# Serial-7-Segment-Shield.net
KiCad netlist of a schematic drawn in EAGLE
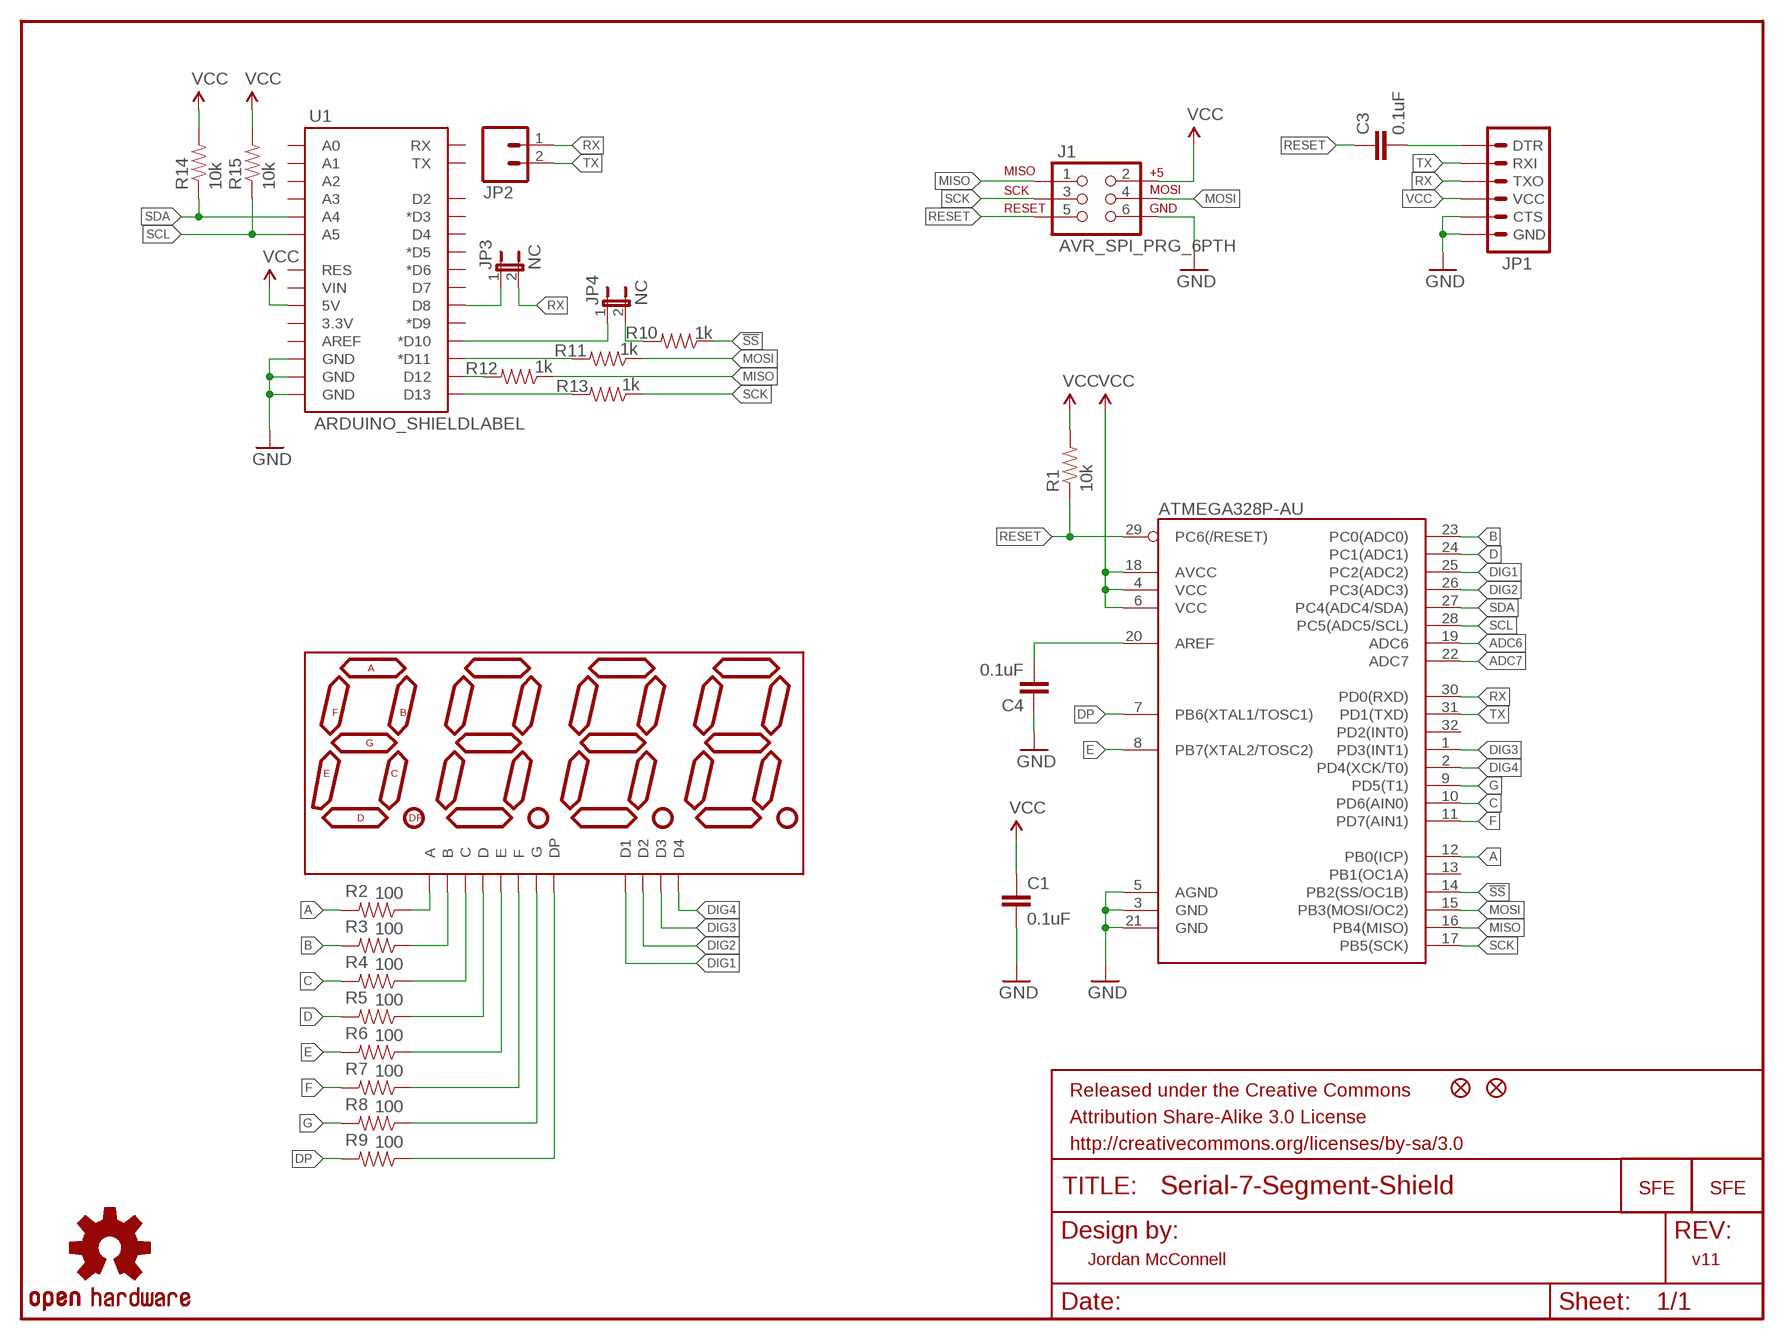
[diagram p0: schematic, sheet 1]

(export (version "E")
  (design (tool "Eeschema 10.0.6"))
  (components
    (comp (ref "ATMEGA328P-AU")
      (value "ATMEGA328P-AU")
      (footprint "eagle-import:TQFP32-08")
      (libsource (lib "eagle-import") (part "ATMEGA168"))
    )
    (comp (ref "C1")
      (value "0.1uF")
      (footprint "eagle-import:0603-CAP")
      (libsource (lib "eagle-import") (part "CAP0603-CAP"))
    )
    (comp (ref "C3")
      (value "0.1uF")
      (footprint "eagle-import:0603-CAP")
      (libsource (lib "eagle-import") (part "SparkFun-Passives_CAP0603-CAP"))
    )
    (comp (ref "C4")
      (value "0.1uF")
      (footprint "eagle-import:0603-CAP")
      (libsource (lib "eagle-import") (part "SparkFun-Passives_CAP0603-CAP"))
    )
    (comp (ref "FRAME1")
      (value "FRAME-LETTER")
      (footprint "eagle-import:CREATIVE_COMMONS")
      (libsource (lib "eagle-import") (part "FRAME-LETTER"))
    )
    (comp (ref "J1")
      (value "AVR_SPI_PRG_6PTH")
      (footprint "eagle-import:2X3")
      (libsource (lib "eagle-import") (part "AVR_SPI_PRG_6PTH"))
    )
    (comp (ref "JP1")
      (value "ARDUINO_SERIAL_PROGRAMPTH")
      (footprint "eagle-import:1X06")
      (libsource (lib "eagle-import") (part "ARDUINO_SERIAL_PROGRAMPTH"))
    )
    (comp (ref "JP2")
      (value "M02PTH")
      (footprint "eagle-import:1X02")
      (libsource (lib "eagle-import") (part "M02PTH"))
    )
    (comp (ref "JP3")
      (value "NC")
      (footprint "eagle-import:SJ_2S")
      (libsource (lib "eagle-import") (part "JUMPER-2SMD-NC"))
    )
    (comp (ref "JP4")
      (value "NC")
      (footprint "eagle-import:SJ_2S")
      (libsource (lib "eagle-import") (part "JUMPER-2SMD-NC"))
    )
    (comp (ref "JP9")
      (value "FIDUCIALUFIDUCIAL")
      (footprint "eagle-import:MICRO-FIDUCIAL")
      (libsource (lib "eagle-import") (part "FIDUCIALUFIDUCIAL"))
    )
    (comp (ref "JP10")
      (value "FIDUCIALUFIDUCIAL")
      (footprint "eagle-import:MICRO-FIDUCIAL")
      (libsource (lib "eagle-import") (part "FIDUCIALUFIDUCIAL"))
    )
    (comp (ref "LOGO1")
      (value "LOGO-SFENEW")
      (footprint "eagle-import:SFE-NEW-WEBLOGO")
      (libsource (lib "eagle-import") (part "LOGO-SFENEW"))
    )
    (comp (ref "LOGO2")
      (value "LOGO-SFENEW")
      (footprint "eagle-import:SFE-NEW-WEBLOGO")
      (libsource (lib "eagle-import") (part "LOGO-SFENEW"))
    )
    (comp (ref "R1")
      (value "10k")
      (footprint "eagle-import:0603-RES")
      (libsource (lib "eagle-import") (part "RESISTOR0603-RES"))
    )
    (comp (ref "R2")
      (value "100")
      (footprint "eagle-import:0603-RES")
      (libsource (lib "eagle-import") (part "RESISTOR0603-RES"))
    )
    (comp (ref "R3")
      (value "100")
      (footprint "eagle-import:0603-RES")
      (libsource (lib "eagle-import") (part "RESISTOR0603-RES"))
    )
    (comp (ref "R4")
      (value "100")
      (footprint "eagle-import:0603-RES")
      (libsource (lib "eagle-import") (part "RESISTOR0603-RES"))
    )
    (comp (ref "R5")
      (value "100")
      (footprint "eagle-import:0603-RES")
      (libsource (lib "eagle-import") (part "RESISTOR0603-RES"))
    )
    (comp (ref "R6")
      (value "100")
      (footprint "eagle-import:0603-RES")
      (libsource (lib "eagle-import") (part "RESISTOR0603-RES"))
    )
    (comp (ref "R7")
      (value "100")
      (footprint "eagle-import:0603-RES")
      (libsource (lib "eagle-import") (part "RESISTOR0603-RES"))
    )
    (comp (ref "R8")
      (value "100")
      (footprint "eagle-import:0603-RES")
      (libsource (lib "eagle-import") (part "RESISTOR0603-RES"))
    )
    (comp (ref "R9")
      (value "100")
      (footprint "eagle-import:0603-RES")
      (libsource (lib "eagle-import") (part "RESISTOR0603-RES"))
    )
    (comp (ref "R10")
      (value "1k")
      (footprint "eagle-import:0603-RES")
      (libsource (lib "eagle-import") (part "RESISTOR0603-RES"))
    )
    (comp (ref "R11")
      (value "1k")
      (footprint "eagle-import:0603-RES")
      (libsource (lib "eagle-import") (part "RESISTOR0603-RES"))
    )
    (comp (ref "R12")
      (value "1k")
      (footprint "eagle-import:0603-RES")
      (libsource (lib "eagle-import") (part "RESISTOR0603-RES"))
    )
    (comp (ref "R13")
      (value "1k")
      (footprint "eagle-import:0603-RES")
      (libsource (lib "eagle-import") (part "RESISTOR0603-RES"))
    )
    (comp (ref "R14")
      (value "10k")
      (footprint "eagle-import:0603-RES")
      (libsource (lib "eagle-import") (part "RESISTOR0603-RES"))
    )
    (comp (ref "R15")
      (value "10k")
      (footprint "eagle-import:0603-RES")
      (libsource (lib "eagle-import") (part "RESISTOR0603-RES"))
    )
    (comp (ref "U$1")
      (value "7-SEGMENT-4DIGIT-COUNTERPTH")
      (footprint "eagle-import:7-SEGMENT-4DIGIT-COUNTER")
      (libsource (lib "eagle-import") (part "7-SEGMENT-4DIGIT-COUNTERPTH"))
    )
    (comp (ref "U$4")
      (value "OSHW-LOGOS")
      (footprint "eagle-import:OSHW-LOGO-S")
      (libsource (lib "eagle-import") (part "OSHW-LOGOS"))
    )
    (comp (ref "U1")
      (value "ARDUINO_SHIELDLABEL")
      (footprint "eagle-import:DUEMILANOVE_SHIELD")
      (libsource (lib "eagle-import") (part "ARDUINO_SHIELDLABEL"))
    )
  )
  (nets
    (net (code "1") (name "/~{SS}") (class "Default")
      (node (ref "ATMEGA328P-AU") (pin "14") (pinfunction "PB2(SS/OC1B)_14") (pintype "bidirectional"))
      (node (ref "R10") (pin "1") (pinfunction "1_1") (pintype "passive"))
    )
    (net (code "2") (name "A") (class "Default")
      (node (ref "ATMEGA328P-AU") (pin "12") (pinfunction "PB0(ICP)_12") (pintype "bidirectional"))
      (node (ref "R2") (pin "2") (pinfunction "2_2") (pintype "passive"))
    )
    (net (code "3") (name "ADC6") (class "Default")
      (node (ref "ATMEGA328P-AU") (pin "19") (pinfunction "ADC6_19") (pintype "bidirectional"))
    )
    (net (code "4") (name "ADC7") (class "Default")
      (node (ref "ATMEGA328P-AU") (pin "22") (pinfunction "ADC7_22") (pintype "bidirectional"))
    )
    (net (code "5") (name "B") (class "Default")
      (node (ref "ATMEGA328P-AU") (pin "23") (pinfunction "PC0(ADC0)_23") (pintype "bidirectional"))
      (node (ref "R3") (pin "2") (pinfunction "2_2") (pintype "passive"))
    )
    (net (code "6") (name "C") (class "Default")
      (node (ref "ATMEGA328P-AU") (pin "10") (pinfunction "PD6(AIN0)_10") (pintype "bidirectional"))
      (node (ref "R4") (pin "2") (pinfunction "2_2") (pintype "passive"))
    )
    (net (code "7") (name "D") (class "Default")
      (node (ref "ATMEGA328P-AU") (pin "24") (pinfunction "PC1(ADC1)_24") (pintype "bidirectional"))
      (node (ref "R5") (pin "2") (pinfunction "2_2") (pintype "passive"))
    )
    (net (code "8") (name "DIG1") (class "Default")
      (node (ref "ATMEGA328P-AU") (pin "25") (pinfunction "PC2(ADC2)_25") (pintype "bidirectional"))
      (node (ref "U$1") (pin "12") (pinfunction "D1_12") (pintype "bidirectional"))
    )
    (net (code "9") (name "DIG2") (class "Default")
      (node (ref "ATMEGA328P-AU") (pin "26") (pinfunction "PC3(ADC3)_26") (pintype "bidirectional"))
      (node (ref "U$1") (pin "9") (pinfunction "D2_9") (pintype "bidirectional"))
    )
    (net (code "10") (name "DIG3") (class "Default")
      (node (ref "ATMEGA328P-AU") (pin "1") (pinfunction "PD3(INT1)_1") (pintype "bidirectional"))
      (node (ref "U$1") (pin "8") (pinfunction "D3_8") (pintype "bidirectional"))
    )
    (net (code "11") (name "DIG4") (class "Default")
      (node (ref "ATMEGA328P-AU") (pin "2") (pinfunction "PD4(XCK/T0)_2") (pintype "bidirectional"))
      (node (ref "U$1") (pin "6") (pinfunction "D4_6") (pintype "bidirectional"))
    )
    (net (code "12") (name "DP") (class "Default")
      (node (ref "ATMEGA328P-AU") (pin "7") (pinfunction "PB6(XTAL1/TOSC1)_7") (pintype "bidirectional"))
      (node (ref "R9") (pin "2") (pinfunction "2_2") (pintype "passive"))
    )
    (net (code "13") (name "E") (class "Default")
      (node (ref "ATMEGA328P-AU") (pin "8") (pinfunction "PB7(XTAL2/TOSC2)_8") (pintype "bidirectional"))
      (node (ref "R6") (pin "2") (pinfunction "2_2") (pintype "passive"))
    )
    (net (code "14") (name "F") (class "Default")
      (node (ref "ATMEGA328P-AU") (pin "11") (pinfunction "PD7(AIN1)_11") (pintype "bidirectional"))
      (node (ref "R7") (pin "2") (pinfunction "2_2") (pintype "passive"))
    )
    (net (code "15") (name "G") (class "Default")
      (node (ref "ATMEGA328P-AU") (pin "9") (pinfunction "PD5(T1)_9") (pintype "bidirectional"))
      (node (ref "R8") (pin "2") (pinfunction "2_2") (pintype "passive"))
    )
    (net (code "16") (name "GND") (class "Default")
      (node (ref "ATMEGA328P-AU") (pin "21") (pinfunction "GND_21") (pintype "bidirectional"))
      (node (ref "ATMEGA328P-AU") (pin "3") (pinfunction "GND_3") (pintype "bidirectional"))
      (node (ref "ATMEGA328P-AU") (pin "5") (pinfunction "AGND_5") (pintype "bidirectional"))
      (node (ref "C1") (pin "2") (pinfunction "2_2") (pintype "passive"))
      (node (ref "C4") (pin "1") (pinfunction "1_1") (pintype "passive"))
      (node (ref "J1") (pin "6") (pinfunction "6_6") (pintype "passive"))
      (node (ref "JP1") (pin "5") (pinfunction "CTS_5") (pintype "passive"))
      (node (ref "JP1") (pin "6") (pinfunction "GND_6") (pintype "passive"))
      (node (ref "U1") (pin "GND@0") (pinfunction "GND_GND@0") (pintype "bidirectional"))
      (node (ref "U1") (pin "GND@1") (pinfunction "GND_GND@1") (pintype "bidirectional"))
      (node (ref "U1") (pin "GND@2") (pinfunction "GND_GND@2") (pintype "bidirectional"))
    )
    (net (code "17") (name "MISO") (class "Default")
      (node (ref "ATMEGA328P-AU") (pin "16") (pinfunction "PB4(MISO)_16") (pintype "bidirectional"))
      (node (ref "J1") (pin "1") (pinfunction "1_1") (pintype "passive"))
      (node (ref "R12") (pin "1") (pinfunction "1_1") (pintype "passive"))
    )
    (net (code "18") (name "MOSI") (class "Default")
      (node (ref "ATMEGA328P-AU") (pin "15") (pinfunction "PB3(MOSI/OC2)_15") (pintype "bidirectional"))
      (node (ref "J1") (pin "4") (pinfunction "4_4") (pintype "passive"))
      (node (ref "R11") (pin "1") (pinfunction "1_1") (pintype "passive"))
    )
    (net (code "19") (name "Net-(ATMEGA328P-AU-AREF)") (class "Default")
      (node (ref "ATMEGA328P-AU") (pin "20") (pinfunction "AREF_20") (pintype "bidirectional"))
      (node (ref "C4") (pin "2") (pinfunction "2_2") (pintype "passive"))
    )
    (net (code "20") (name "Net-(JP1-DTR)") (class "Default")
      (node (ref "C3") (pin "2") (pinfunction "2_2") (pintype "passive"))
      (node (ref "JP1") (pin "1") (pinfunction "DTR_1") (pintype "passive"))
    )
    (net (code "21") (name "Net-(JP3-Pad1)") (class "Default")
      (node (ref "JP3") (pin "1") (pinfunction "1_1") (pintype "passive"))
      (node (ref "U1") (pin "D8") (pinfunction "D8_D8") (pintype "bidirectional"))
    )
    (net (code "22") (name "Net-(JP4-Pad2)") (class "Default")
      (node (ref "JP4") (pin "2") (pinfunction "2_2") (pintype "passive"))
      (node (ref "R10") (pin "2") (pinfunction "2_2") (pintype "passive"))
    )
    (net (code "23") (name "Net-(R12-Pad2)") (class "Default")
      (node (ref "R12") (pin "2") (pinfunction "2_2") (pintype "passive"))
      (node (ref "U1") (pin "D12") (pinfunction "D12_D12") (pintype "bidirectional"))
    )
    (net (code "24") (name "Net-(R13-Pad2)") (class "Default")
      (node (ref "R13") (pin "2") (pinfunction "2_2") (pintype "passive"))
      (node (ref "U1") (pin "D13") (pinfunction "D13_D13") (pintype "bidirectional"))
    )
    (net (code "25") (name "Net-(U$1-A)") (class "Default")
      (node (ref "R2") (pin "1") (pinfunction "1_1") (pintype "passive"))
      (node (ref "U$1") (pin "11") (pinfunction "A_11") (pintype "bidirectional"))
    )
    (net (code "26") (name "Net-(U$1-B)") (class "Default")
      (node (ref "R3") (pin "1") (pinfunction "1_1") (pintype "passive"))
      (node (ref "U$1") (pin "7") (pinfunction "B_7") (pintype "bidirectional"))
    )
    (net (code "27") (name "Net-(U$1-C)") (class "Default")
      (node (ref "R4") (pin "1") (pinfunction "1_1") (pintype "passive"))
      (node (ref "U$1") (pin "4") (pinfunction "C_4") (pintype "bidirectional"))
    )
    (net (code "28") (name "Net-(U$1-D)") (class "Default")
      (node (ref "R5") (pin "1") (pinfunction "1_1") (pintype "passive"))
      (node (ref "U$1") (pin "2") (pinfunction "D_2") (pintype "bidirectional"))
    )
    (net (code "29") (name "Net-(U$1-DP)") (class "Default")
      (node (ref "R9") (pin "1") (pinfunction "1_1") (pintype "passive"))
      (node (ref "U$1") (pin "3") (pinfunction "DP_3") (pintype "bidirectional"))
    )
    (net (code "30") (name "Net-(U$1-E)") (class "Default")
      (node (ref "R6") (pin "1") (pinfunction "1_1") (pintype "passive"))
      (node (ref "U$1") (pin "1") (pinfunction "E_1") (pintype "bidirectional"))
    )
    (net (code "31") (name "Net-(U$1-F)") (class "Default")
      (node (ref "R7") (pin "1") (pinfunction "1_1") (pintype "passive"))
      (node (ref "U$1") (pin "10") (pinfunction "F_10") (pintype "bidirectional"))
    )
    (net (code "32") (name "Net-(U$1-G)") (class "Default")
      (node (ref "R8") (pin "1") (pinfunction "1_1") (pintype "passive"))
      (node (ref "U$1") (pin "5") (pinfunction "G_5") (pintype "bidirectional"))
    )
    (net (code "33") (name "Net-(U1-*D10)") (class "Default")
      (node (ref "JP4") (pin "1") (pinfunction "1_1") (pintype "passive"))
      (node (ref "U1") (pin "D10") (pinfunction "*D10_D10") (pintype "bidirectional"))
    )
    (net (code "34") (name "Net-(U1-*D11)") (class "Default")
      (node (ref "R11") (pin "2") (pinfunction "2_2") (pintype "passive"))
      (node (ref "U1") (pin "D11") (pinfunction "*D11_D11") (pintype "bidirectional"))
    )
    (net (code "35") (name "RESET") (class "Default")
      (node (ref "ATMEGA328P-AU") (pin "29") (pinfunction "PC6(/RESET)_29") (pintype "bidirectional"))
      (node (ref "C3") (pin "1") (pinfunction "1_1") (pintype "passive"))
      (node (ref "J1") (pin "5") (pinfunction "5_5") (pintype "passive"))
      (node (ref "R1") (pin "1") (pinfunction "1_1") (pintype "passive"))
    )
    (net (code "36") (name "RX") (class "Default")
      (node (ref "ATMEGA328P-AU") (pin "30") (pinfunction "PD0(RXD)_30") (pintype "bidirectional"))
      (node (ref "JP1") (pin "3") (pinfunction "TXO_3") (pintype "passive"))
      (node (ref "JP2") (pin "1") (pinfunction "1_1") (pintype "passive"))
      (node (ref "JP3") (pin "2") (pinfunction "2_2") (pintype "passive"))
    )
    (net (code "37") (name "SCK") (class "Default")
      (node (ref "ATMEGA328P-AU") (pin "17") (pinfunction "PB5(SCK)_17") (pintype "bidirectional"))
      (node (ref "J1") (pin "3") (pinfunction "3_3") (pintype "passive"))
      (node (ref "R13") (pin "1") (pinfunction "1_1") (pintype "passive"))
    )
    (net (code "38") (name "SCL") (class "Default")
      (node (ref "ATMEGA328P-AU") (pin "28") (pinfunction "PC5(ADC5/SCL)_28") (pintype "bidirectional"))
      (node (ref "R15") (pin "1") (pinfunction "1_1") (pintype "passive"))
      (node (ref "U1") (pin "A5") (pinfunction "A5_A5") (pintype "bidirectional"))
    )
    (net (code "39") (name "SDA") (class "Default")
      (node (ref "ATMEGA328P-AU") (pin "27") (pinfunction "PC4(ADC4/SDA)_27") (pintype "bidirectional"))
      (node (ref "R14") (pin "1") (pinfunction "1_1") (pintype "passive"))
      (node (ref "U1") (pin "A4") (pinfunction "A4_A4") (pintype "bidirectional"))
    )
    (net (code "40") (name "TX") (class "Default")
      (node (ref "ATMEGA328P-AU") (pin "31") (pinfunction "PD1(TXD)_31") (pintype "bidirectional"))
      (node (ref "JP1") (pin "2") (pinfunction "RXI_2") (pintype "passive"))
      (node (ref "JP2") (pin "2") (pinfunction "2_2") (pintype "passive"))
    )
    (net (code "41") (name "VCC") (class "Default")
      (node (ref "ATMEGA328P-AU") (pin "18") (pinfunction "AVCC_18") (pintype "bidirectional"))
      (node (ref "ATMEGA328P-AU") (pin "4") (pinfunction "VCC_4") (pintype "bidirectional"))
      (node (ref "ATMEGA328P-AU") (pin "6") (pinfunction "VCC_6") (pintype "bidirectional"))
      (node (ref "C1") (pin "1") (pinfunction "1_1") (pintype "passive"))
      (node (ref "J1") (pin "2") (pinfunction "2_2") (pintype "passive"))
      (node (ref "JP1") (pin "4") (pinfunction "VCC_4") (pintype "passive"))
      (node (ref "R1") (pin "2") (pinfunction "2_2") (pintype "passive"))
      (node (ref "R14") (pin "2") (pinfunction "2_2") (pintype "passive"))
      (node (ref "R15") (pin "2") (pinfunction "2_2") (pintype "passive"))
      (node (ref "U1") (pin "5V") (pinfunction "5V_5V") (pintype "bidirectional"))
    )
    (net (code "42") (name "unconnected-(ATMEGA328P-AU-PB1(OC1A)-Pad13)") (class "Default")
      (node (ref "ATMEGA328P-AU") (pin "13") (pinfunction "PB1(OC1A)_13") (pintype "bidirectional"))
    )
    (net (code "43") (name "unconnected-(ATMEGA328P-AU-PD2(INT0)-Pad32)") (class "Default")
      (node (ref "ATMEGA328P-AU") (pin "32") (pinfunction "PD2(INT0)_32") (pintype "bidirectional"))
    )
    (net (code "44") (name "unconnected-(U1-*D3-PadD3)") (class "Default")
      (node (ref "U1") (pin "D3") (pinfunction "*D3_D3") (pintype "bidirectional"))
    )
    (net (code "45") (name "unconnected-(U1-*D5-PadD5)") (class "Default")
      (node (ref "U1") (pin "D5") (pinfunction "*D5_D5") (pintype "bidirectional"))
    )
    (net (code "46") (name "unconnected-(U1-*D6-PadD6)") (class "Default")
      (node (ref "U1") (pin "D6") (pinfunction "*D6_D6") (pintype "bidirectional"))
    )
    (net (code "47") (name "unconnected-(U1-*D9-PadD9)") (class "Default")
      (node (ref "U1") (pin "D9") (pinfunction "*D9_D9") (pintype "bidirectional"))
    )
    (net (code "48") (name "unconnected-(U1-Pad3.3V)") (class "Default")
      (node (ref "U1") (pin "3.3V") (pinfunction "3.3V_3.3V") (pintype "bidirectional"))
    )
    (net (code "49") (name "unconnected-(U1-PadA0)") (class "Default")
      (node (ref "U1") (pin "A0") (pinfunction "A0_A0") (pintype "bidirectional"))
    )
    (net (code "50") (name "unconnected-(U1-PadA1)") (class "Default")
      (node (ref "U1") (pin "A1") (pinfunction "A1_A1") (pintype "bidirectional"))
    )
    (net (code "51") (name "unconnected-(U1-PadA2)") (class "Default")
      (node (ref "U1") (pin "A2") (pinfunction "A2_A2") (pintype "bidirectional"))
    )
    (net (code "52") (name "unconnected-(U1-PadA3)") (class "Default")
      (node (ref "U1") (pin "A3") (pinfunction "A3_A3") (pintype "bidirectional"))
    )
    (net (code "53") (name "unconnected-(U1-PadAREF)") (class "Default")
      (node (ref "U1") (pin "AREF") (pinfunction "AREF_AREF") (pintype "bidirectional"))
    )
    (net (code "54") (name "unconnected-(U1-PadD2)") (class "Default")
      (node (ref "U1") (pin "D2") (pinfunction "D2_D2") (pintype "bidirectional"))
    )
    (net (code "55") (name "unconnected-(U1-PadD4)") (class "Default")
      (node (ref "U1") (pin "D4") (pinfunction "D4_D4") (pintype "bidirectional"))
    )
    (net (code "56") (name "unconnected-(U1-PadD7)") (class "Default")
      (node (ref "U1") (pin "D7") (pinfunction "D7_D7") (pintype "bidirectional"))
    )
    (net (code "57") (name "unconnected-(U1-PadRES)") (class "Default")
      (node (ref "U1") (pin "RES") (pinfunction "RES_RES") (pintype "bidirectional"))
    )
    (net (code "58") (name "unconnected-(U1-PadRX)") (class "Default")
      (node (ref "U1") (pin "RX") (pinfunction "RX_RX") (pintype "bidirectional"))
    )
    (net (code "59") (name "unconnected-(U1-PadTX)") (class "Default")
      (node (ref "U1") (pin "TX") (pinfunction "TX_TX") (pintype "bidirectional"))
    )
    (net (code "60") (name "unconnected-(U1-PadVIN)") (class "Default")
      (node (ref "U1") (pin "VIN") (pinfunction "VIN_VIN") (pintype "bidirectional"))
    )
  )
)
